# MotorCell_2.net
KiCad netlist of a schematic drawn in Altium Designer
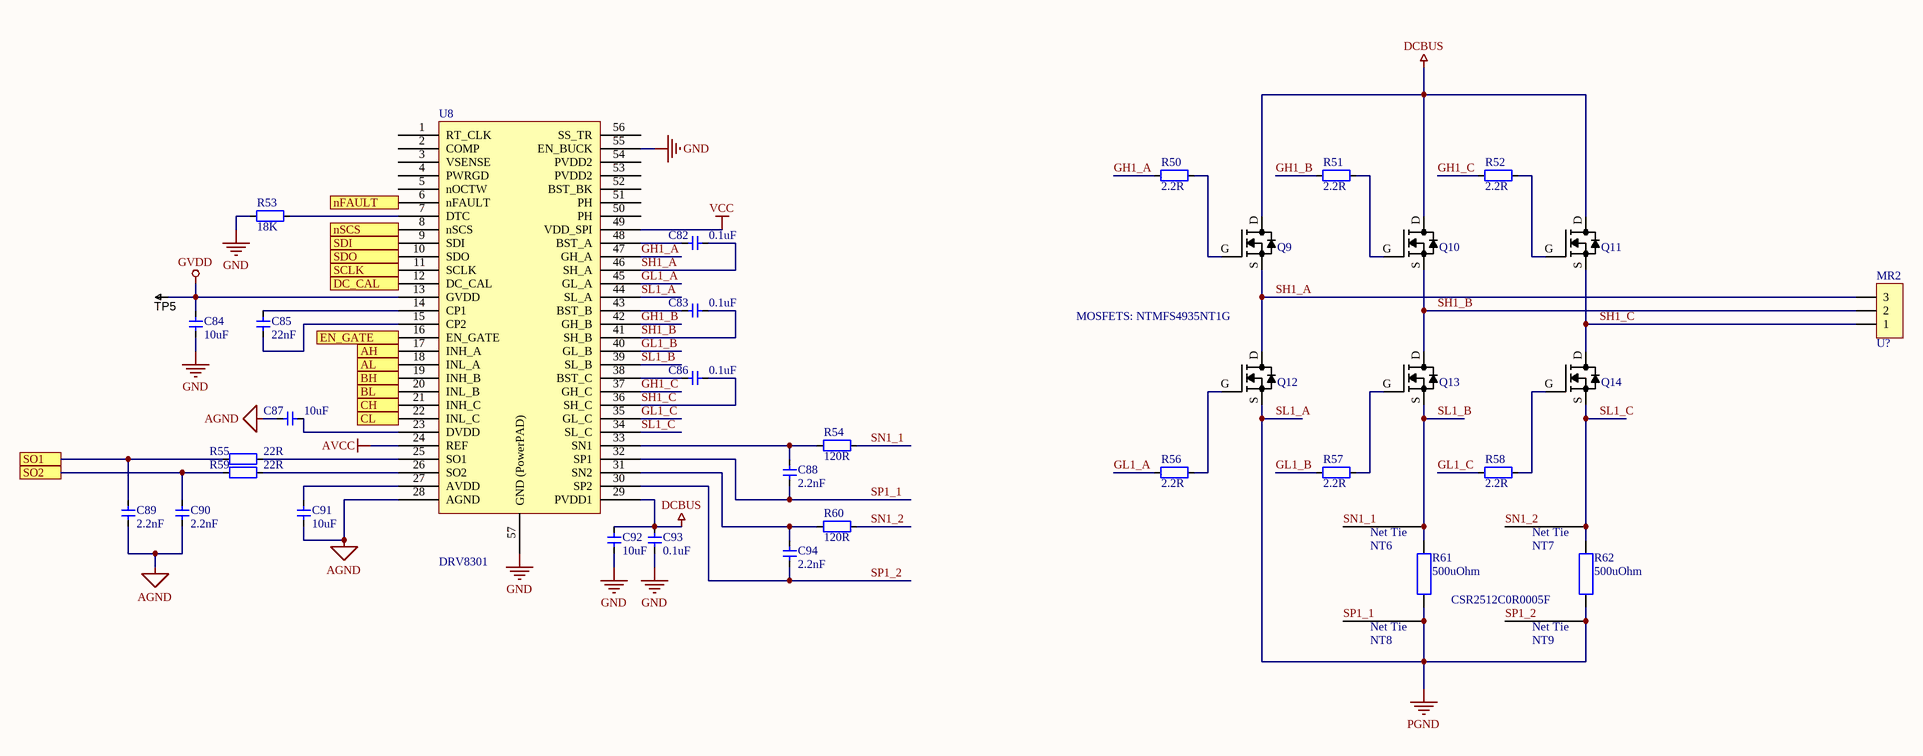
[diagram p0: MotorCell_2.SchDoc]

(export (version "E")
  (design (tool "Eeschema 10.0.6"))
  (components
    (comp (ref "C82")
      (value "0.1uF")
      (footprint "CAP_0603")
      (description "Capacitor")
      (libsource (lib "Ctrl_FOC") (part "电容-0603"))
    )
    (comp (ref "C83")
      (value "0.1uF")
      (footprint "CAP_0603")
      (description "Capacitor")
      (libsource (lib "Ctrl_FOC") (part "电容-0603"))
    )
    (comp (ref "C84")
      (value "10uF")
      (footprint "CAP_0402")
      (description "Capacitor")
      (libsource (lib "Ctrl_FOC") (part "电容-0402"))
    )
    (comp (ref "C85")
      (value "22nF")
      (footprint "CAP_0402")
      (description "Capacitor")
      (libsource (lib "Ctrl_FOC") (part "电容-0402"))
    )
    (comp (ref "C86")
      (value "0.1uF")
      (footprint "CAP_0603")
      (description "Capacitor")
      (libsource (lib "Ctrl_FOC") (part "电容-0603"))
    )
    (comp (ref "C87")
      (value "10uF")
      (footprint "CAP_0402")
      (description "Capacitor")
      (libsource (lib "Ctrl_FOC") (part "电容-0402"))
    )
    (comp (ref "C88")
      (value "2.2nF")
      (footprint "CAP_0402")
      (description "Capacitor")
      (libsource (lib "Ctrl_FOC") (part "电容-0402"))
    )
    (comp (ref "C89")
      (value "2.2nF")
      (footprint "CAP_0402")
      (description "Capacitor")
      (libsource (lib "Ctrl_FOC") (part "电容-0402"))
    )
    (comp (ref "C90")
      (value "2.2nF")
      (footprint "CAP_0402")
      (description "Capacitor")
      (libsource (lib "Ctrl_FOC") (part "电容-0402"))
    )
    (comp (ref "C91")
      (value "10uF")
      (footprint "CAP_0402")
      (description "Capacitor")
      (libsource (lib "Ctrl_FOC") (part "电容-0402"))
    )
    (comp (ref "C92")
      (value "10uF")
      (footprint "CAP_0603")
      (description "Capacitor")
      (libsource (lib "Ctrl_FOC") (part "电容-0603"))
    )
    (comp (ref "C93")
      (value "0.1uF")
      (footprint "CAP_0603")
      (description "Capacitor")
      (libsource (lib "Ctrl_FOC") (part "电容-0603"))
    )
    (comp (ref "C94")
      (value "2.2nF")
      (footprint "CAP_0402")
      (description "Capacitor")
      (libsource (lib "Ctrl_FOC") (part "电容-0402"))
    )
    (comp (ref "MR2")
      (value "U?")
      (footprint "MR30PW-M")
      (description "MR30PW-M 三芯")
      (libsource (lib "VectorController") (part "MR30PW-M"))
    )
    (comp (ref "NT6")
      (value "0.25mm")
      (footprint "NetTie_0.25mm")
      (libsource (lib "Ctrl_FOC") (part "NetTie_0.25mm"))
    )
    (comp (ref "NT7")
      (value "0.25mm")
      (footprint "NetTie_0.25mm")
      (libsource (lib "Ctrl_FOC") (part "NetTie_0.25mm"))
    )
    (comp (ref "NT8")
      (value "0.25mm")
      (footprint "NetTie_0.25mm")
      (libsource (lib "Ctrl_FOC") (part "NetTie_0.25mm"))
    )
    (comp (ref "NT9")
      (value "0.25mm")
      (footprint "NetTie_0.25mm")
      (libsource (lib "Ctrl_FOC") (part "NetTie_0.25mm"))
    )
    (comp (ref "Q9")
      (value "NTMFS4935NT1G")
      (footprint "SO8FL")
      (description "MOSFET N-CH 30V 13A SO8FL")
      (fields (field (name "MANUFACTURER") "ON Semiconductor"))
      (libsource (lib "Ctrl_FOC") (part "NTMFS4935NT1G"))
    )
    (comp (ref "Q10")
      (value "NTMFS4935NT1G")
      (footprint "SO8FL")
      (description "MOSFET N-CH 30V 13A SO8FL")
      (fields (field (name "MANUFACTURER") "ON Semiconductor"))
      (libsource (lib "Ctrl_FOC") (part "NTMFS4935NT1G"))
    )
    (comp (ref "Q11")
      (value "NTMFS4935NT1G")
      (footprint "SO8FL")
      (description "MOSFET N-CH 30V 13A SO8FL")
      (fields (field (name "MANUFACTURER") "ON Semiconductor"))
      (libsource (lib "Ctrl_FOC") (part "NTMFS4935NT1G"))
    )
    (comp (ref "Q12")
      (value "NTMFS4935NT1G")
      (footprint "SO8FL")
      (description "MOSFET N-CH 30V 13A SO8FL")
      (fields (field (name "MANUFACTURER") "ON Semiconductor"))
      (libsource (lib "Ctrl_FOC") (part "NTMFS4935NT1G"))
    )
    (comp (ref "Q13")
      (value "NTMFS4935NT1G")
      (footprint "SO8FL")
      (description "MOSFET N-CH 30V 13A SO8FL")
      (fields (field (name "MANUFACTURER") "ON Semiconductor"))
      (libsource (lib "Ctrl_FOC") (part "NTMFS4935NT1G"))
    )
    (comp (ref "Q14")
      (value "NTMFS4935NT1G")
      (footprint "SO8FL")
      (description "MOSFET N-CH 30V 13A SO8FL")
      (fields (field (name "MANUFACTURER") "ON Semiconductor"))
      (libsource (lib "Ctrl_FOC") (part "NTMFS4935NT1G"))
    )
    (comp (ref "R50")
      (value "2.2R")
      (footprint "RES_0402")
      (description "Resistor")
      (libsource (lib "Ctrl_FOC") (part "电阻-0402"))
    )
    (comp (ref "R51")
      (value "2.2R")
      (footprint "RES_0402")
      (description "Resistor")
      (libsource (lib "Ctrl_FOC") (part "电阻-0402"))
    )
    (comp (ref "R52")
      (value "2.2R")
      (footprint "RES_0402")
      (description "Resistor")
      (libsource (lib "Ctrl_FOC") (part "电阻-0402"))
    )
    (comp (ref "R53")
      (value "18K")
      (footprint "RES_0402")
      (description "Resistor")
      (libsource (lib "Ctrl_FOC") (part "电阻-0402"))
    )
    (comp (ref "R54")
      (value "120R")
      (footprint "RES_0402")
      (description "Resistor")
      (libsource (lib "Ctrl_FOC") (part "电阻-0402"))
    )
    (comp (ref "R55")
      (value "22R")
      (footprint "RES_0402")
      (description "Resistor")
      (libsource (lib "Ctrl_FOC") (part "电阻-0402"))
    )
    (comp (ref "R56")
      (value "2.2R")
      (footprint "RES_0402")
      (description "Resistor")
      (libsource (lib "Ctrl_FOC") (part "电阻-0402"))
    )
    (comp (ref "R57")
      (value "2.2R")
      (footprint "RES_0402")
      (description "Resistor")
      (libsource (lib "Ctrl_FOC") (part "电阻-0402"))
    )
    (comp (ref "R58")
      (value "2.2R")
      (footprint "RES_0402")
      (description "Resistor")
      (libsource (lib "Ctrl_FOC") (part "电阻-0402"))
    )
    (comp (ref "R59")
      (value "22R")
      (footprint "RES_0402")
      (description "Resistor")
      (libsource (lib "Ctrl_FOC") (part "电阻-0402"))
    )
    (comp (ref "R60")
      (value "120R")
      (footprint "RES_0402")
      (description "Resistor")
      (libsource (lib "Ctrl_FOC") (part "电阻-0402"))
    )
    (comp (ref "R61")
      (value "500uOhm")
      (footprint "RESC6432X09N")
      (description "RES SMD 0.0005 OHM 1% 3W 2512")
      (fields (field (name "MANUFACTURER") "Riedon") (field (name "TOLERANCE") "±1%"))
      (libsource (lib "Ctrl_FOC") (part "CSR2512C0R0005F"))
    )
    (comp (ref "R62")
      (value "500uOhm")
      (footprint "RESC6432X09N")
      (description "RES SMD 0.0005 OHM 1% 3W 2512")
      (fields (field (name "MANUFACTURER") "Riedon") (field (name "TOLERANCE") "±1%"))
      (libsource (lib "Ctrl_FOC") (part "CSR2512C0R0005F"))
    )
    (comp (ref "TP5")
      (value "TESTPOINT")
      (footprint "TP-R30")
      (description "SMD test pin")
      (libsource (lib "Ctrl_FOC") (part "TESTPOINT"))
    )
    (comp (ref "U8")
      (value "DRV8301")
      (footprint "TSSOP50P810X120_HS-57N")
      (description "MOTOR DRIVER, 3PH, 56HTSSOP")
      (libsource (lib "Ctrl_FOC") (part "DRV8301"))
    )
  )
  (nets
    (net (code "1") (name "/AH") (class "Default")
      (node (ref "U8") (pin "17") (pinfunction "INH_A_17") (pintype "passive"))
    )
    (net (code "2") (name "/AL") (class "Default")
      (node (ref "U8") (pin "18") (pinfunction "INL_A_18") (pintype "passive"))
    )
    (net (code "3") (name "/BH") (class "Default")
      (node (ref "U8") (pin "19") (pinfunction "INH_B_19") (pintype "passive"))
    )
    (net (code "4") (name "/BL") (class "Default")
      (node (ref "U8") (pin "20") (pinfunction "INL_B_20") (pintype "passive"))
    )
    (net (code "5") (name "/CH") (class "Default")
      (node (ref "U8") (pin "21") (pinfunction "INH_C_21") (pintype "passive"))
    )
    (net (code "6") (name "/CL") (class "Default")
      (node (ref "U8") (pin "22") (pinfunction "INL_C_22") (pintype "passive"))
    )
    (net (code "7") (name "/DC_CAL") (class "Default")
      (node (ref "U8") (pin "12") (pinfunction "DC_CAL_12") (pintype "passive"))
    )
    (net (code "8") (name "/EN_GATE") (class "Default")
      (node (ref "U8") (pin "16") (pinfunction "EN_GATE_16") (pintype "passive"))
    )
    (net (code "9") (name "/GH1_A") (class "Default")
      (node (ref "R50") (pin "1") (pinfunction "1_1") (pintype "passive"))
      (node (ref "U8") (pin "47") (pinfunction "GH_A_47") (pintype "passive"))
    )
    (net (code "10") (name "/GH1_B") (class "Default")
      (node (ref "R51") (pin "1") (pinfunction "1_1") (pintype "passive"))
      (node (ref "U8") (pin "42") (pinfunction "GH_B_42") (pintype "passive"))
    )
    (net (code "11") (name "/GH1_C") (class "Default")
      (node (ref "R52") (pin "1") (pinfunction "1_1") (pintype "passive"))
      (node (ref "U8") (pin "37") (pinfunction "GH_C_37") (pintype "passive"))
    )
    (net (code "12") (name "/GL1_A") (class "Default")
      (node (ref "R56") (pin "1") (pinfunction "1_1") (pintype "passive"))
      (node (ref "U8") (pin "45") (pinfunction "GL_A_45") (pintype "passive"))
    )
    (net (code "13") (name "/GL1_B") (class "Default")
      (node (ref "R57") (pin "1") (pinfunction "1_1") (pintype "passive"))
      (node (ref "U8") (pin "40") (pinfunction "GL_B_40") (pintype "passive"))
    )
    (net (code "14") (name "/GL1_C") (class "Default")
      (node (ref "R58") (pin "1") (pinfunction "1_1") (pintype "passive"))
      (node (ref "U8") (pin "35") (pinfunction "GL_C_35") (pintype "passive"))
    )
    (net (code "15") (name "/SCLK") (class "Default")
      (node (ref "U8") (pin "11") (pinfunction "SCLK_11") (pintype "passive"))
    )
    (net (code "16") (name "/SDI") (class "Default")
      (node (ref "U8") (pin "9") (pinfunction "SDI_9") (pintype "passive"))
    )
    (net (code "17") (name "/SDO") (class "Default")
      (node (ref "U8") (pin "10") (pinfunction "SDO_10") (pintype "passive"))
    )
    (net (code "18") (name "/SH1_A") (class "Default")
      (node (ref "C82") (pin "2") (pinfunction "2_2") (pintype "passive"))
      (node (ref "MR2") (pin "3") (pinfunction "3_3") (pintype "passive"))
      (node (ref "Q12") (pin "D") (pinfunction "D_D") (pintype "passive"))
      (node (ref "Q9") (pin "S") (pinfunction "S_S") (pintype "passive"))
      (node (ref "U8") (pin "46") (pinfunction "SH_A_46") (pintype "passive"))
    )
    (net (code "19") (name "/SH1_B") (class "Default")
      (node (ref "C83") (pin "2") (pinfunction "2_2") (pintype "passive"))
      (node (ref "MR2") (pin "2") (pinfunction "2_2") (pintype "passive"))
      (node (ref "Q10") (pin "S") (pinfunction "S_S") (pintype "passive"))
      (node (ref "Q13") (pin "D") (pinfunction "D_D") (pintype "passive"))
      (node (ref "U8") (pin "41") (pinfunction "SH_B_41") (pintype "passive"))
    )
    (net (code "20") (name "/SH1_C") (class "Default")
      (node (ref "C86") (pin "2") (pinfunction "2_2") (pintype "passive"))
      (node (ref "MR2") (pin "1") (pinfunction "1_1") (pintype "passive"))
      (node (ref "Q11") (pin "S") (pinfunction "S_S") (pintype "passive"))
      (node (ref "Q14") (pin "D") (pinfunction "D_D") (pintype "passive"))
      (node (ref "U8") (pin "36") (pinfunction "SH_C_36") (pintype "passive"))
    )
    (net (code "21") (name "/SL1_B") (class "Default")
      (node (ref "NT6") (pin "2") (pintype "passive"))
      (node (ref "Q13") (pin "S") (pinfunction "S_S") (pintype "passive"))
      (node (ref "R61") (pin "2") (pinfunction "0_2") (pintype "passive"))
      (node (ref "U8") (pin "39") (pinfunction "SL_B_39") (pintype "passive"))
    )
    (net (code "22") (name "/SL1_C") (class "Default")
      (node (ref "NT7") (pin "2") (pintype "passive"))
      (node (ref "Q14") (pin "S") (pinfunction "S_S") (pintype "passive"))
      (node (ref "R62") (pin "2") (pinfunction "0_2") (pintype "passive"))
      (node (ref "U8") (pin "34") (pinfunction "SL_C_34") (pintype "passive"))
    )
    (net (code "23") (name "/SN1_1") (class "Default")
      (node (ref "NT6") (pin "1") (pintype "passive"))
      (node (ref "R54") (pin "2") (pinfunction "2_2") (pintype "passive"))
    )
    (net (code "24") (name "/SN1_2") (class "Default")
      (node (ref "NT7") (pin "1") (pintype "passive"))
      (node (ref "R60") (pin "2") (pinfunction "2_2") (pintype "passive"))
    )
    (net (code "25") (name "/SO1") (class "Default")
      (node (ref "C89") (pin "2") (pinfunction "2_2") (pintype "passive"))
      (node (ref "R55") (pin "1") (pinfunction "1_1") (pintype "passive"))
    )
    (net (code "26") (name "/SO2") (class "Default")
      (node (ref "C90") (pin "2") (pinfunction "2_2") (pintype "passive"))
      (node (ref "R59") (pin "1") (pinfunction "1_1") (pintype "passive"))
    )
    (net (code "27") (name "/SP1_1") (class "Default")
      (node (ref "C88") (pin "1") (pinfunction "1_1") (pintype "passive"))
      (node (ref "NT8") (pin "1") (pintype "passive"))
      (node (ref "U8") (pin "32") (pinfunction "SP1_32") (pintype "passive"))
    )
    (net (code "28") (name "/SP1_2") (class "Default")
      (node (ref "C94") (pin "1") (pinfunction "1_1") (pintype "passive"))
      (node (ref "NT9") (pin "1") (pintype "passive"))
      (node (ref "U8") (pin "30") (pinfunction "SP2_30") (pintype "passive"))
    )
    (net (code "29") (name "/nFAULT") (class "Default")
      (node (ref "U8") (pin "6") (pinfunction "nFAULT_6") (pintype "passive"))
    )
    (net (code "30") (name "/nSCS") (class "Default")
      (node (ref "U8") (pin "8") (pinfunction "nSCS_8") (pintype "passive"))
    )
    (net (code "31") (name "AGND") (class "Default")
      (node (ref "C87") (pin "2") (pinfunction "2_2") (pintype "passive"))
      (node (ref "C89") (pin "1") (pinfunction "1_1") (pintype "passive"))
      (node (ref "C90") (pin "1") (pinfunction "1_1") (pintype "passive"))
      (node (ref "C91") (pin "1") (pinfunction "1_1") (pintype "passive"))
      (node (ref "U8") (pin "28") (pinfunction "AGND_28") (pintype "passive"))
    )
    (net (code "32") (name "AVCC") (class "Default")
      (node (ref "U8") (pin "24") (pinfunction "REF_24") (pintype "passive"))
    )
    (net (code "33") (name "DCBUS") (class "Default")
      (node (ref "C92") (pin "2") (pinfunction "2_2") (pintype "passive"))
      (node (ref "C93") (pin "2") (pinfunction "2_2") (pintype "passive"))
      (node (ref "Q10") (pin "D") (pinfunction "D_D") (pintype "passive"))
      (node (ref "Q11") (pin "D") (pinfunction "D_D") (pintype "passive"))
      (node (ref "Q9") (pin "D") (pinfunction "D_D") (pintype "passive"))
      (node (ref "U8") (pin "29") (pinfunction "PVDD1_29") (pintype "passive"))
    )
    (net (code "34") (name "GND") (class "Default")
      (node (ref "C84") (pin "1") (pinfunction "1_1") (pintype "passive"))
      (node (ref "C92") (pin "1") (pinfunction "1_1") (pintype "passive"))
      (node (ref "C93") (pin "1") (pinfunction "1_1") (pintype "passive"))
      (node (ref "R53") (pin "1") (pinfunction "1_1") (pintype "passive"))
      (node (ref "U8") (pin "55") (pinfunction "EN_BUCK_55") (pintype "passive"))
      (node (ref "U8") (pin "57") (pinfunction "GND_(PowerPAD)_57") (pintype "passive"))
    )
    (net (code "35") (name "GVDD") (class "Default")
      (node (ref "C84") (pin "2") (pinfunction "2_2") (pintype "passive"))
      (node (ref "TP5") (pin "1") (pintype "passive"))
      (node (ref "U8") (pin "13") (pinfunction "GVDD_13") (pintype "passive"))
    )
    (net (code "36") (name "Net-(Q9-PadG)") (class "Default")
      (node (ref "Q9") (pin "G") (pinfunction "G_G") (pintype "passive"))
      (node (ref "R50") (pin "2") (pinfunction "2_2") (pintype "passive"))
    )
    (net (code "37") (name "Net-(Q10-PadG)") (class "Default")
      (node (ref "Q10") (pin "G") (pinfunction "G_G") (pintype "passive"))
      (node (ref "R51") (pin "2") (pinfunction "2_2") (pintype "passive"))
    )
    (net (code "38") (name "Net-(Q11-PadG)") (class "Default")
      (node (ref "Q11") (pin "G") (pinfunction "G_G") (pintype "passive"))
      (node (ref "R52") (pin "2") (pinfunction "2_2") (pintype "passive"))
    )
    (net (code "39") (name "Net-(Q12-PadG)") (class "Default")
      (node (ref "Q12") (pin "G") (pinfunction "G_G") (pintype "passive"))
      (node (ref "R56") (pin "2") (pinfunction "2_2") (pintype "passive"))
    )
    (net (code "40") (name "Net-(Q13-PadG)") (class "Default")
      (node (ref "Q13") (pin "G") (pinfunction "G_G") (pintype "passive"))
      (node (ref "R57") (pin "2") (pinfunction "2_2") (pintype "passive"))
    )
    (net (code "41") (name "Net-(Q14-PadG)") (class "Default")
      (node (ref "Q14") (pin "G") (pinfunction "G_G") (pintype "passive"))
      (node (ref "R58") (pin "2") (pinfunction "2_2") (pintype "passive"))
    )
    (net (code "42") (name "Net-(U8-AVDD)") (class "Default")
      (node (ref "C91") (pin "2") (pinfunction "2_2") (pintype "passive"))
      (node (ref "U8") (pin "27") (pinfunction "AVDD_27") (pintype "passive"))
    )
    (net (code "43") (name "Net-(U8-BST_A)") (class "Default")
      (node (ref "C82") (pin "1") (pinfunction "1_1") (pintype "passive"))
      (node (ref "U8") (pin "48") (pinfunction "BST_A_48") (pintype "passive"))
    )
    (net (code "44") (name "Net-(U8-BST_B)") (class "Default")
      (node (ref "C83") (pin "1") (pinfunction "1_1") (pintype "passive"))
      (node (ref "U8") (pin "43") (pinfunction "BST_B_43") (pintype "passive"))
    )
    (net (code "45") (name "Net-(U8-BST_C)") (class "Default")
      (node (ref "C86") (pin "1") (pinfunction "1_1") (pintype "passive"))
      (node (ref "U8") (pin "38") (pinfunction "BST_C_38") (pintype "passive"))
    )
    (net (code "46") (name "Net-(U8-CP1)") (class "Default")
      (node (ref "C85") (pin "1") (pinfunction "1_1") (pintype "passive"))
      (node (ref "U8") (pin "14") (pinfunction "CP1_14") (pintype "passive"))
    )
    (net (code "47") (name "Net-(U8-CP2)") (class "Default")
      (node (ref "C85") (pin "2") (pinfunction "2_2") (pintype "passive"))
      (node (ref "U8") (pin "15") (pinfunction "CP2_15") (pintype "passive"))
    )
    (net (code "48") (name "Net-(U8-DTC)") (class "Default")
      (node (ref "R53") (pin "2") (pinfunction "2_2") (pintype "passive"))
      (node (ref "U8") (pin "7") (pinfunction "DTC_7") (pintype "passive"))
    )
    (net (code "49") (name "Net-(U8-DVDD)") (class "Default")
      (node (ref "C87") (pin "1") (pinfunction "1_1") (pintype "passive"))
      (node (ref "U8") (pin "23") (pinfunction "DVDD_23") (pintype "passive"))
    )
    (net (code "50") (name "Net-(U8-SN1)") (class "Default")
      (node (ref "C88") (pin "2") (pinfunction "2_2") (pintype "passive"))
      (node (ref "R54") (pin "1") (pinfunction "1_1") (pintype "passive"))
      (node (ref "U8") (pin "33") (pinfunction "SN1_33") (pintype "passive"))
    )
    (net (code "51") (name "Net-(U8-SN2)") (class "Default")
      (node (ref "C94") (pin "2") (pinfunction "2_2") (pintype "passive"))
      (node (ref "R60") (pin "1") (pinfunction "1_1") (pintype "passive"))
      (node (ref "U8") (pin "31") (pinfunction "SN2_31") (pintype "passive"))
    )
    (net (code "52") (name "Net-(U8-SO1)") (class "Default")
      (node (ref "R55") (pin "2") (pinfunction "2_2") (pintype "passive"))
      (node (ref "U8") (pin "25") (pinfunction "SO1_25") (pintype "passive"))
    )
    (net (code "53") (name "Net-(U8-SO2)") (class "Default")
      (node (ref "R59") (pin "2") (pinfunction "2_2") (pintype "passive"))
      (node (ref "U8") (pin "26") (pinfunction "SO2_26") (pintype "passive"))
    )
    (net (code "54") (name "PGND") (class "Default")
      (node (ref "NT8") (pin "2") (pintype "passive"))
      (node (ref "NT9") (pin "2") (pintype "passive"))
      (node (ref "Q12") (pin "S") (pinfunction "S_S") (pintype "passive"))
      (node (ref "R61") (pin "1") (pinfunction "0_1") (pintype "passive"))
      (node (ref "R62") (pin "1") (pinfunction "0_1") (pintype "passive"))
      (node (ref "U8") (pin "44") (pinfunction "SL_A_44") (pintype "passive"))
    )
    (net (code "55") (name "VCC") (class "Default")
      (node (ref "U8") (pin "49") (pinfunction "VDD_SPI_49") (pintype "passive"))
    )
    (net (code "56") (name "unconnected-(U8-BST_BK-Pad52)") (class "Default")
      (node (ref "U8") (pin "52") (pinfunction "BST_BK_52") (pintype "passive"))
    )
    (net (code "57") (name "unconnected-(U8-COMP-Pad2)") (class "Default")
      (node (ref "U8") (pin "2") (pinfunction "COMP_2") (pintype "passive"))
    )
    (net (code "58") (name "unconnected-(U8-PH-Pad50)") (class "Default")
      (node (ref "U8") (pin "50") (pinfunction "PH_50") (pintype "passive"))
    )
    (net (code "59") (name "unconnected-(U8-PH-Pad51)") (class "Default")
      (node (ref "U8") (pin "51") (pinfunction "PH_51") (pintype "passive"))
    )
    (net (code "60") (name "unconnected-(U8-PVDD2-Pad53)") (class "Default")
      (node (ref "U8") (pin "53") (pinfunction "PVDD2_53") (pintype "passive"))
    )
    (net (code "61") (name "unconnected-(U8-PVDD2-Pad54)") (class "Default")
      (node (ref "U8") (pin "54") (pinfunction "PVDD2_54") (pintype "passive"))
    )
    (net (code "62") (name "unconnected-(U8-PWRGD-Pad4)") (class "Default")
      (node (ref "U8") (pin "4") (pinfunction "PWRGD_4") (pintype "passive"))
    )
    (net (code "63") (name "unconnected-(U8-RT_CLK-Pad1)") (class "Default")
      (node (ref "U8") (pin "1") (pinfunction "RT_CLK_1") (pintype "passive"))
    )
    (net (code "64") (name "unconnected-(U8-SS_TR-Pad56)") (class "Default")
      (node (ref "U8") (pin "56") (pinfunction "SS_TR_56") (pintype "passive"))
    )
    (net (code "65") (name "unconnected-(U8-VSENSE-Pad3)") (class "Default")
      (node (ref "U8") (pin "3") (pinfunction "VSENSE_3") (pintype "passive"))
    )
    (net (code "66") (name "unconnected-(U8-nOCTW-Pad5)") (class "Default")
      (node (ref "U8") (pin "5") (pinfunction "nOCTW_5") (pintype "passive"))
    )
  )
)
